# NanoPiAir_SDR_Shield_V1.net
KiCad netlist of a schematic drawn in Altium Designer
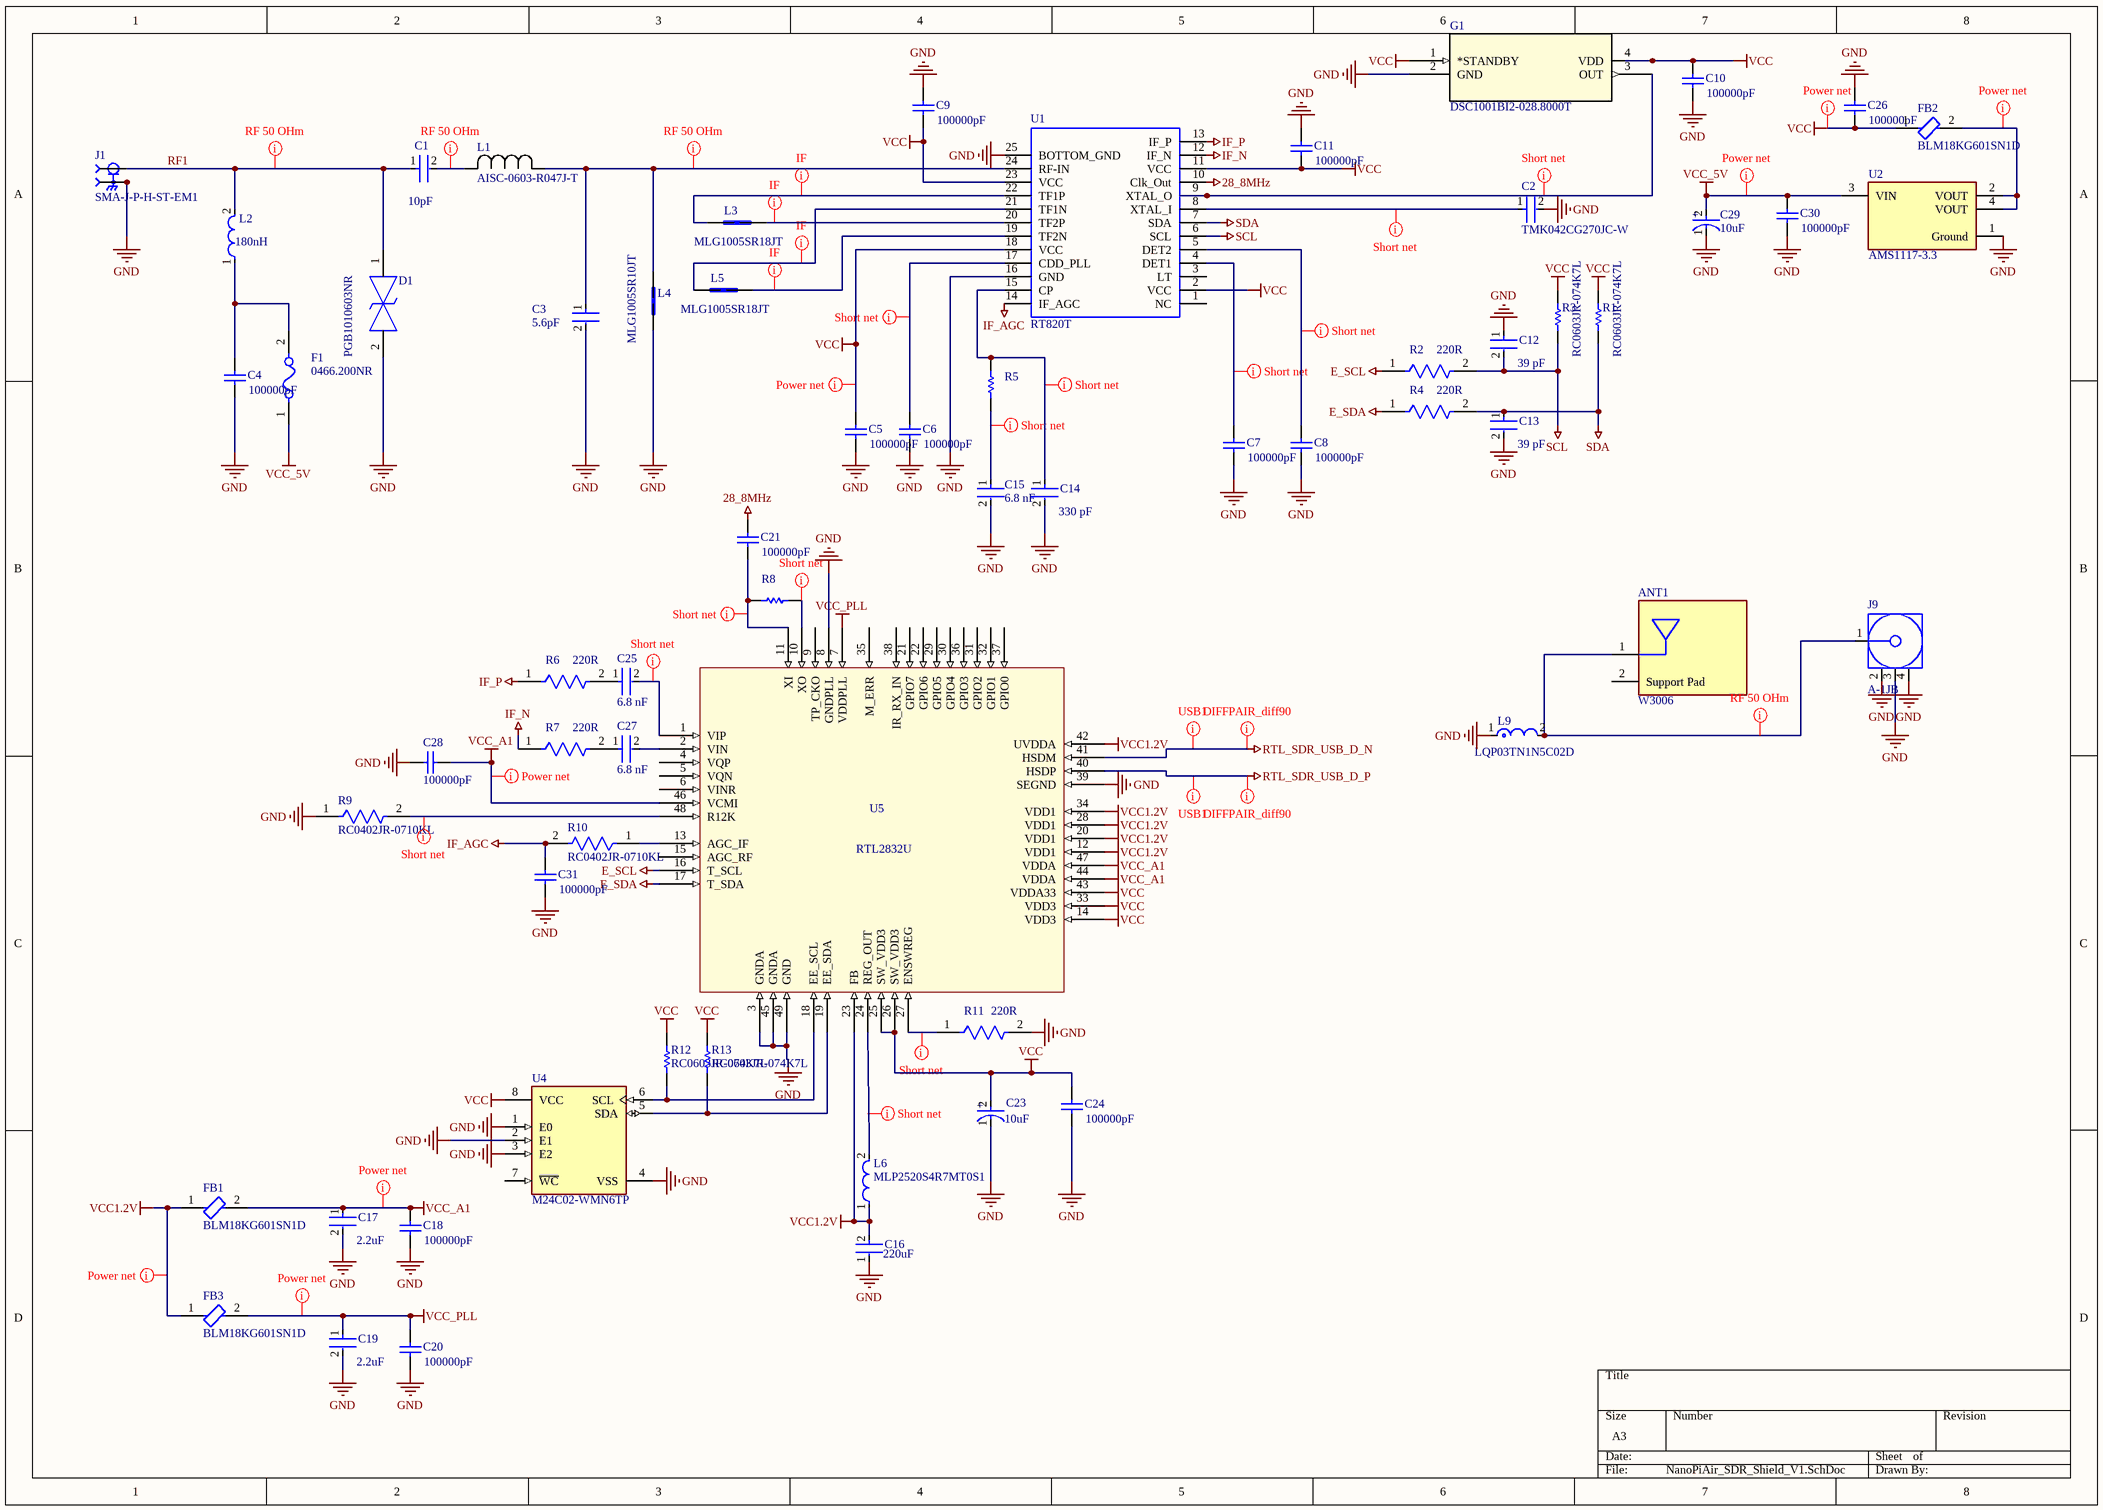
[diagram p0: NanoPiAir_SDR_Shield_V1.SchDoc]

(export (version "E")
  (design (tool "Eeschema 10.0.6"))
  (components
    (comp (ref "ANT1")
      (value "W3006")
      (footprint "FP-W3006-0")
      (description "RF ANT 2.4GHZ/5.5GHZ CHIP SLD")
      (libsource (lib "Altium Content Vault") (part "7e9f1c3ea5b015cef85830d8f377364"))
    )
    (comp (ref "C1")
      (value "GJM1555C1H100GB01D")
      (footprint "FP-GJM155-0_05-IPC_B")
      (description "Multi-Layer Ceramic Capacitor 10pF C0G  ±2% 0402 Paper T/R")
      (fields (field (name "CAPACITANCE") "10pF") (field (name "TOLERANCE") "2%"))
      (libsource (lib "Altium Content Vault") (part "02cd4be3c70576c341d710602a673aa"))
    )
    (comp (ref "C2")
      (value "TMK042CG270JC-W")
      (footprint "FP-01005-L_0_4_0_02-W_0_2-MFG")
      (description "None")
      (libsource (lib "Schlib1") (part "CMP-14477-000467-2"))
    )
    (comp (ref "C3")
      (value "GJM1555C1H5R6CB01D")
      (footprint "FP-GJM155-0_05-IPC_B")
      (description "Multi-Layer Ceramic Capacitor 5.6pF C0G  ±0.25pF 0402 Paper T/R")
      (fields (field (name "CAPACITANCE") "5.6pF") (field (name "VOLTAGE") "50V"))
      (libsource (lib "Altium Content Vault") (part "02cd4be3c70576c341d710602a673aa"))
    )
    (comp (ref "C4")
      (value "CL05B104KO5NNNC")
      (footprint "CAPC1050X55X23ML05T13")
      (description "Chip Capacitor, 100 nF, +/- 10%, 16 V, -55 to 125 degC, 0402 (1005 Metric), RoHS, Tape and Reel")
      (fields
        (field (name "MANUFACTURER") "Samsung Electro-Mechanics")
        (field (name "CAPACITANCE") "100000pF")
      )
      (libsource (lib "Altium Content Vault") (part "CAP-NP-2"))
    )
    (comp (ref "C5")
      (value "CL05B104KO5NNNC")
      (footprint "CAPC1050X55X23ML05T13")
      (description "Chip Capacitor, 100 nF, +/- 10%, 16 V, -55 to 125 degC, 0402 (1005 Metric), RoHS, Tape and Reel")
      (fields
        (field (name "MANUFACTURER") "Samsung Electro-Mechanics")
        (field (name "CAPACITANCE") "100000pF")
      )
      (libsource (lib "Altium Content Vault") (part "CAP-NP-2"))
    )
    (comp (ref "C6")
      (value "CL05B104KO5NNNC")
      (footprint "CAPC1050X55X23ML05T13")
      (description "Chip Capacitor, 100 nF, +/- 10%, 16 V, -55 to 125 degC, 0402 (1005 Metric), RoHS, Tape and Reel")
      (fields
        (field (name "MANUFACTURER") "Samsung Electro-Mechanics")
        (field (name "CAPACITANCE") "100000pF")
      )
      (libsource (lib "Altium Content Vault") (part "CAP-NP-2"))
    )
    (comp (ref "C7")
      (value "CL05B104KO5NNNC")
      (footprint "CAPC1050X55X23ML05T13")
      (description "Chip Capacitor, 100 nF, +/- 10%, 16 V, -55 to 125 degC, 0402 (1005 Metric), RoHS, Tape and Reel")
      (fields
        (field (name "MANUFACTURER") "Samsung Electro-Mechanics")
        (field (name "CAPACITANCE") "100000pF")
      )
      (libsource (lib "Altium Content Vault") (part "CAP-NP-2"))
    )
    (comp (ref "C8")
      (value "CL05B104KO5NNNC")
      (footprint "CAPC1050X55X23ML05T13")
      (description "Chip Capacitor, 100 nF, +/- 10%, 16 V, -55 to 125 degC, 0402 (1005 Metric), RoHS, Tape and Reel")
      (fields
        (field (name "MANUFACTURER") "Samsung Electro-Mechanics")
        (field (name "CAPACITANCE") "100000pF")
      )
      (libsource (lib "Altium Content Vault") (part "CAP-NP-2"))
    )
    (comp (ref "C9")
      (value "CL05B104KO5NNNC")
      (footprint "CAPC1050X55X23ML05T13")
      (description "Chip Capacitor, 100 nF, +/- 10%, 16 V, -55 to 125 degC, 0402 (1005 Metric), RoHS, Tape and Reel")
      (fields
        (field (name "MANUFACTURER") "Samsung Electro-Mechanics")
        (field (name "CAPACITANCE") "100000pF")
      )
      (libsource (lib "Altium Content Vault") (part "CAP-NP-2"))
    )
    (comp (ref "C10")
      (value "CL05B104KO5NNNC")
      (footprint "CAPC1050X55X23ML05T13")
      (description "Chip Capacitor, 100 nF, +/- 10%, 16 V, -55 to 125 degC, 0402 (1005 Metric), RoHS, Tape and Reel")
      (fields
        (field (name "MANUFACTURER") "Samsung Electro-Mechanics")
        (field (name "CAPACITANCE") "100000pF")
      )
      (libsource (lib "Altium Content Vault") (part "CAP-NP-2"))
    )
    (comp (ref "C11")
      (value "CL05B104KO5NNNC")
      (footprint "CAPC1050X55X23ML05T13")
      (description "Chip Capacitor, 100 nF, +/- 10%, 16 V, -55 to 125 degC, 0402 (1005 Metric), RoHS, Tape and Reel")
      (fields
        (field (name "MANUFACTURER") "Samsung Electro-Mechanics")
        (field (name "CAPACITANCE") "100000pF")
      )
      (libsource (lib "Altium Content Vault") (part "CAP-NP-2"))
    )
    (comp (ref "C12")
      (value "AC0402JRNPO9BN390")
      (footprint "FP-AC0402-0_5-MFG")
      (description "AC0402 39 pF NPO 5.00% 50 V")
      (fields
        (field (name "CAPACITANCE") "39 pF")
        (field (name "MANUFACTURER") "Yageo")
        (field (name "TOLERANCE") "0.05")
      )
      (libsource (lib "Altium Content Vault") (part "11868f565c42a9108669ba33697ecf6"))
    )
    (comp (ref "C13")
      (value "AC0402JRNPO9BN390")
      (footprint "FP-AC0402-0_5-MFG")
      (description "AC0402 39 pF NPO 5.00% 50 V")
      (fields
        (field (name "CAPACITANCE") "39 pF")
        (field (name "MANUFACTURER") "Yageo")
        (field (name "TOLERANCE") "0.05")
      )
      (libsource (lib "Altium Content Vault") (part "11868f565c42a9108669ba33697ecf6"))
    )
    (comp (ref "C14")
      (value "CC0402KRX7R7BB331")
      (footprint "FP-CC0402-MFG")
      (description "CC0402 330 pF X7R 10.00% 16 V")
      (fields
        (field (name "CAPACITANCE") "330 pF")
        (field (name "OCTOPART") "https://octopart.com/cc0402krx7r7bb331-yageo-87194285")
        (field (name "TOLERANCE") "0.1")
      )
      (libsource (lib "Altium Content Vault") (part "11868f565c42a9108669ba33697ecf6"))
    )
    (comp (ref "C15")
      (value "6.8 nF")
      (footprint "FP-CC0402-MFG")
      (description "CAP CER 6800PF 50V X7R 0402")
      (fields
        (field (name "MANUFACTURER") "YAGEO")
        (field (name "OCTOPART") "https://octopart.com/cc0402krx7r9bb682-yageo-9291871")
      )
      (libsource (lib "Altium Content Vault") (part "11868f565c42a9108669ba33697ecf6"))
    )
    (comp (ref "C16")
      (value "GRM31CR60J227ME11L")
      (footprint "FP-GRM31C-0_3-e0_3_0_9-IPC_C")
      (description "Chip Multilayer Ceramic Capacitors for General Purpose, 1206, 220uF, X5R, 15%, 20%, 6.3V")
      (fields (field (name "CAPACITANCE") "220uF") (field (name "TOLERANCE") "20%"))
      (libsource (lib "Altium Content Vault") (part "f23184f103b6ebe33a8c269c53dcba6"))
    )
    (comp (ref "C17")
      (value "GRM155R61A225KE95D")
      (footprint "FP-GRM155-0_05-MFG")
      (description "CAP CER 2.2UF 10V X5R 0402")
      (fields (field (name "CAPACITANCE") "2.2uF") (field (name "TOLERANCE") "10%"))
      (libsource (lib "Altium Content Vault") (part "b4654b650e69147ec39a6b967a45e02"))
    )
    (comp (ref "C18")
      (value "CL05B104KO5NNNC")
      (footprint "CAPC1050X55X23ML05T13")
      (description "Chip Capacitor, 100 nF, +/- 10%, 16 V, -55 to 125 degC, 0402 (1005 Metric), RoHS, Tape and Reel")
      (fields
        (field (name "MANUFACTURER") "Samsung Electro-Mechanics")
        (field (name "CAPACITANCE") "100000pF")
      )
      (libsource (lib "Altium Content Vault") (part "CAP-NP-2"))
    )
    (comp (ref "C19")
      (value "GRM155R61A225KE95D")
      (footprint "FP-GRM155-0_05-MFG")
      (description "CAP CER 2.2UF 10V X5R 0402")
      (fields (field (name "CAPACITANCE") "2.2uF") (field (name "TOLERANCE") "10%"))
      (libsource (lib "Altium Content Vault") (part "b4654b650e69147ec39a6b967a45e02"))
    )
    (comp (ref "C20")
      (value "CL05B104KO5NNNC")
      (footprint "CAPC1050X55X23ML05T13")
      (description "Chip Capacitor, 100 nF, +/- 10%, 16 V, -55 to 125 degC, 0402 (1005 Metric), RoHS, Tape and Reel")
      (fields
        (field (name "MANUFACTURER") "Samsung Electro-Mechanics")
        (field (name "CAPACITANCE") "100000pF")
      )
      (libsource (lib "Altium Content Vault") (part "CAP-NP-2"))
    )
    (comp (ref "C21")
      (value "CL05B104KO5NNNC")
      (footprint "CAPC1050X55X23ML05T13")
      (description "Chip Capacitor, 100 nF, +/- 10%, 16 V, -55 to 125 degC, 0402 (1005 Metric), RoHS, Tape and Reel")
      (fields
        (field (name "MANUFACTURER") "Samsung Electro-Mechanics")
        (field (name "CAPACITANCE") "100000pF")
      )
      (libsource (lib "Altium Content Vault") (part "CAP-NP-2"))
    )
    (comp (ref "C23")
      (value "TAJA106K010RNJ")
      (footprint "FP-TAJA-MFG")
      (description "10uF 10V  ±10% 3Ω 1206  SMD Tantalum Capacitor")
      (fields
        (field (name "TOLERANCE") "10%")
        (field (name "CAPACITANCE") "10uF")
        (field (name "VOLTAGE") "10V")
      )
      (libsource (lib "Altium Content Vault") (part "203bc49f2ac43e59fd269a8c329ed05"))
    )
    (comp (ref "C24")
      (value "CL05B104KO5NNNC")
      (footprint "CAPC1050X55X23ML05T13")
      (description "Chip Capacitor, 100 nF, +/- 10%, 16 V, -55 to 125 degC, 0402 (1005 Metric), RoHS, Tape and Reel")
      (fields
        (field (name "MANUFACTURER") "Samsung Electro-Mechanics")
        (field (name "CAPACITANCE") "100000pF")
      )
      (libsource (lib "Altium Content Vault") (part "CAP-NP-2"))
    )
    (comp (ref "C25")
      (value "6.8 nF")
      (footprint "FP-CC0402-MFG")
      (description "CAP CER 6800PF 50V X7R 0402")
      (fields
        (field (name "MANUFACTURER") "YAGEO")
        (field (name "OCTOPART") "https://octopart.com/cc0402krx7r9bb682-yageo-9291871")
      )
      (libsource (lib "Altium Content Vault") (part "11868f565c42a9108669ba33697ecf6"))
    )
    (comp (ref "C26")
      (value "CL05B104KO5NNNC")
      (footprint "CAPC1050X55X23ML05T13")
      (description "Chip Capacitor, 100 nF, +/- 10%, 16 V, -55 to 125 degC, 0402 (1005 Metric), RoHS, Tape and Reel")
      (fields
        (field (name "MANUFACTURER") "Samsung Electro-Mechanics")
        (field (name "CAPACITANCE") "100000pF")
      )
      (libsource (lib "Altium Content Vault") (part "CAP-NP-2"))
    )
    (comp (ref "C27")
      (value "6.8 nF")
      (footprint "FP-CC0402-MFG")
      (description "CAP CER 6800PF 50V X7R 0402")
      (fields
        (field (name "MANUFACTURER") "YAGEO")
        (field (name "OCTOPART") "https://octopart.com/cc0402krx7r9bb682-yageo-9291871")
      )
      (libsource (lib "Altium Content Vault") (part "11868f565c42a9108669ba33697ecf6"))
    )
    (comp (ref "C28")
      (value "CL05B104KO5NNNC")
      (footprint "CAPC1050X55X23ML05T13")
      (description "Chip Capacitor, 100 nF, +/- 10%, 16 V, -55 to 125 degC, 0402 (1005 Metric), RoHS, Tape and Reel")
      (fields
        (field (name "MANUFACTURER") "Samsung Electro-Mechanics")
        (field (name "CAPACITANCE") "100000pF")
      )
      (libsource (lib "Altium Content Vault") (part "CAP-NP-2"))
    )
    (comp (ref "C29")
      (value "TAJA106K010RNJ")
      (footprint "FP-TAJA-MFG")
      (description "10uF 10V  ±10% 3Ω 1206  SMD Tantalum Capacitor")
      (fields
        (field (name "TOLERANCE") "10%")
        (field (name "CAPACITANCE") "10uF")
        (field (name "VOLTAGE") "10V")
      )
      (libsource (lib "Altium Content Vault") (part "203bc49f2ac43e59fd269a8c329ed05"))
    )
    (comp (ref "C30")
      (value "CL05B104KO5NNNC")
      (footprint "CAPC1050X55X23ML05T13")
      (description "Chip Capacitor, 100 nF, +/- 10%, 16 V, -55 to 125 degC, 0402 (1005 Metric), RoHS, Tape and Reel")
      (fields
        (field (name "MANUFACTURER") "Samsung Electro-Mechanics")
        (field (name "CAPACITANCE") "100000pF")
      )
      (libsource (lib "Altium Content Vault") (part "CAP-NP-2"))
    )
    (comp (ref "C31")
      (value "CL05B104KO5NNNC")
      (footprint "CAPC1050X55X23ML05T13")
      (description "Chip Capacitor, 100 nF, +/- 10%, 16 V, -55 to 125 degC, 0402 (1005 Metric), RoHS, Tape and Reel")
      (fields
        (field (name "MANUFACTURER") "Samsung Electro-Mechanics")
        (field (name "CAPACITANCE") "100000pF")
      )
      (libsource (lib "Altium Content Vault") (part "CAP-NP-2"))
    )
    (comp (ref "D1")
      (value "PGB1010603NR")
      (footprint "PGB1010603MR")
      (description "ESD Suppressors / TVS Diodes 0603 24VDC .06pF")
      (fields (field (name "MOUSER PART NUMBER") "576-PGB1010603NR"))
      (libsource (lib "Schlib1") (part "PGB1010603NR"))
    )
    (comp (ref "F1")
      (value "0466.200NR")
      (footprint "FP-0466-MFG")
      (description "FUSE BOARD MNT 200MA 125VAC/VDC")
      (libsource (lib "Altium Content Vault") (part "5bcf9b9f640e542cf0359d10258e979"))
    )
    (comp (ref "FB1")
      (value "BLM18KG601SN1D")
      (footprint "FP-BLM18-0_15-t0_8-IPC_A")
      (description "Chip Ferrite Bead, 0603, 600Ω @ 100MHz, 0.15Ω, 25%, 1.3A")
      (fields (field (name "TOLERANCE") "25%"))
      (libsource (lib "Altium Content Vault") (part "5f30dd21d616792df468990f7003faa"))
    )
    (comp (ref "FB2")
      (value "BLM18KG601SN1D")
      (footprint "FP-BLM18-0_15-t0_8-IPC_A")
      (description "Chip Ferrite Bead, 0603, 600Ω @ 100MHz, 0.15Ω, 25%, 1.3A")
      (fields (field (name "TOLERANCE") "25%"))
      (libsource (lib "Altium Content Vault") (part "5f30dd21d616792df468990f7003faa"))
    )
    (comp (ref "FB3")
      (value "BLM18KG601SN1D")
      (footprint "FP-BLM18-0_15-t0_8-IPC_A")
      (description "Chip Ferrite Bead, 0603, 600Ω @ 100MHz, 0.15Ω, 25%, 1.3A")
      (fields (field (name "TOLERANCE") "25%"))
      (libsource (lib "Altium Content Vault") (part "5f30dd21d616792df468990f7003faa"))
    )
    (comp (ref "G1")
      (value "DSC1001BI2-028.8000T")
      (footprint "CDFN4_5X3P2_MCH")
      (description "No Description Available")
      (fields (field (name "COPYRIGHT") "Copyright (C) 2023 Ultra Librarian. All rights reserved."))
      (libsource (lib "Schlib1") (part "DSC1001BI2-028.8000T"))
    )
    (comp (ref "J1")
      (value "SMA-J-P-H-ST-EM1")
      (footprint "SAMTEC_SMA-J-P-H-ST-EM1")
      (description "SMA Connector Jack, Female Socket 50Ohm Board Edge, End Launch Solder")
      (libsource (lib "Schlib1") (part "SMA-J-P-H-ST-EM1"))
    )
    (comp (ref "J9")
      (value "A-1JB")
      (footprint "AMPH-A-1JB_V")
      (description "AMC PCB Jack, 0 to 60 GHz, 60 V, -40 to 90 degC, 4-Pin SMD, RoHS, Tape and Reel")
      (fields (field (name "TOLERANCE") "10%"))
      (libsource (lib "Altium Content Vault") (part "CN-S-3F-RF4"))
    )
    (comp (ref "L1")
      (value "AISC-0603-R047J-T")
      (footprint "AISC-0603_ABR")
      (description "No Description Available")
      (fields (field (name "COPYRIGHT") "Copyright (C) 2023 Ultra Librarian. All rights reserved."))
      (libsource (lib "Schlib1") (part "AISC-0603-R047J-T"))
    )
    (comp (ref "L2")
      (value "LQM18NNR18K00D")
      (footprint "FP-LQM18NN_00-IPC_C")
      (description "Multilayer Type Inductor for General Circuits, 0603 (1608), 180nH, 10%, 0.6Ω, 50mA")
      (fields (field (name "INDUCTANCE") "180nH") (field (name "TOLERANCE") "10%"))
      (libsource (lib "Altium Content Vault") (part "725321dda6339637d4d059423bc1c3c"))
    )
    (comp (ref "L3")
      (value "MLG1005SR18JT")
      (footprint "CAPC1005X55N")
      (description "Ind High Frequency Chip Unshielded Multi-Layer 180nH 5% 100MHz 8Q-Factor Ceramic 150mA 0402 T/R")
      (libsource (lib "Schlib1") (part "MLG1005SR18JT"))
    )
    (comp (ref "L4")
      (value "MLG1005SR10JT")
      (footprint "CAPC1005X55N")
      (description "Ind High Frequency Chip Unshielded Multi-Layer 180nH 5% 100MHz 8Q-Factor Ceramic 150mA 0402 T/R")
      (fields (field (name "MP") "MLG1005SR18JT"))
      (libsource (lib "") (part "MLG1005SR18JT_1"))
    )
    (comp (ref "L5")
      (value "MLG1005SR18JT")
      (footprint "CAPC1005X55N")
      (description "Ind High Frequency Chip Unshielded Multi-Layer 180nH 5% 100MHz 8Q-Factor Ceramic 150mA 0402 T/R")
      (libsource (lib "Schlib1") (part "MLG1005SR18JT"))
    )
    (comp (ref "L6")
      (value "MLP2520S4R7MT0S1")
      (footprint "FP-MLP2520M-IPC_C")
      (description "Shielded Multilayer Inductor 4.7uH ±20% 1000mA 169mΩ SMD 1008")
      (fields (field (name "TOLERANCE") "20%"))
      (libsource (lib "Altium Content Vault") (part "725321dda6339637d4d059423bc1c3c"))
    )
    (comp (ref "L9")
      (value "LQP03TN1N5C02D")
      (footprint "FP-LQP03TG_02-IPC_A")
      (description "Film type RF Inductor 1.5nH ±0.2nH 600mA 0.15Ω 0201 (0603)")
      (libsource (lib "Altium Content Vault") (part "4cc4b267dca4c8e51f7102f422741d8"))
    )
    (comp (ref "R1")
      (value "RC0603JR-074K7L")
      (footprint "RESC1608X55X25ML10T15")
      (description "Chip Resistor, 4.7 KOhm, +/- 5%, 100 mW, -55 to 155 degC, 0603 (1608 Metric), RoHS, Tape and Reel")
      (fields (field (name "TOLERANCE") "5%") (field (name "MANUFACTURER") "Yageo"))
      (libsource (lib "Altium Content Vault") (part "RES-2"))
    )
    (comp (ref "R2")
      (value "AC0402FR-07220RL")
      (footprint "FP-AC0402-IPC_C")
      (description "RES 220Ω ±1% 0.063W 0402")
      (fields (field (name "RESISTANCE") "220R") (field (name "TOLERANCE") "1%"))
      (libsource (lib "Altium Content Vault") (part "1029c3af85768c4190bb7ad29bc67b5"))
    )
    (comp (ref "R3")
      (value "RC0603JR-074K7L")
      (footprint "RESC1608X55X25ML10T15")
      (description "Chip Resistor, 4.7 KOhm, +/- 5%, 100 mW, -55 to 155 degC, 0603 (1608 Metric), RoHS, Tape and Reel")
      (fields (field (name "TOLERANCE") "5%") (field (name "MANUFACTURER") "Yageo"))
      (libsource (lib "Altium Content Vault") (part "RES-2"))
    )
    (comp (ref "R4")
      (value "AC0402FR-07220RL")
      (footprint "FP-AC0402-IPC_C")
      (description "RES 220Ω ±1% 0.063W 0402")
      (fields (field (name "RESISTANCE") "220R") (field (name "TOLERANCE") "1%"))
      (libsource (lib "Altium Content Vault") (part "1029c3af85768c4190bb7ad29bc67b5"))
    )
    (comp (ref "R5")
      (value "RK73H1ETTP1801F")
      (footprint "RESC1005X40X25ML10T10")
      (fields (field (name "MANUFACTURER") "KOA Speer"))
      (libsource (lib "Altium Content Vault") (part "RES"))
    )
    (comp (ref "R6")
      (value "AC0402FR-07220RL")
      (footprint "FP-AC0402-IPC_C")
      (description "RES 220Ω ±1% 0.063W 0402")
      (fields (field (name "RESISTANCE") "220R") (field (name "TOLERANCE") "1%"))
      (libsource (lib "Altium Content Vault") (part "1029c3af85768c4190bb7ad29bc67b5"))
    )
    (comp (ref "R7")
      (value "AC0402FR-07220RL")
      (footprint "FP-AC0402-IPC_C")
      (description "RES 220Ω ±1% 0.063W 0402")
      (fields (field (name "RESISTANCE") "220R") (field (name "TOLERANCE") "1%"))
      (libsource (lib "Altium Content Vault") (part "1029c3af85768c4190bb7ad29bc67b5"))
    )
    (comp (ref "R8")
      (value "RC0402JR-07150KL")
      (footprint "RESC1005X40X25ML05T10")
      (fields (field (name "MANUFACTURER") "Yageo / Phycomp"))
      (libsource (lib "Altium Content Vault") (part "RES"))
    )
    (comp (ref "R9")
      (value "RC0402JR-0710KL")
      (footprint "FP-RC0402-0_4-IPC_C")
      (description "RES 10K OHM 5% 1/16W 0402")
      (fields (field (name "TOLERANCE") "5%"))
      (libsource (lib "Altium Content Vault") (part "1029c3af85768c4190bb7ad29bc67b5"))
    )
    (comp (ref "R10")
      (value "RC0402JR-0710KL")
      (footprint "FP-RC0402-0_4-IPC_C")
      (description "RES 10K OHM 5% 1/16W 0402")
      (fields (field (name "TOLERANCE") "5%"))
      (libsource (lib "Altium Content Vault") (part "1029c3af85768c4190bb7ad29bc67b5"))
    )
    (comp (ref "R11")
      (value "AC0402FR-07220RL")
      (footprint "FP-AC0402-IPC_C")
      (description "RES 220Ω ±1% 0.063W 0402")
      (fields (field (name "RESISTANCE") "220R") (field (name "TOLERANCE") "1%"))
      (libsource (lib "Altium Content Vault") (part "1029c3af85768c4190bb7ad29bc67b5"))
    )
    (comp (ref "R12")
      (value "RC0603JR-074K7L")
      (footprint "RESC1608X55X25ML10T15")
      (description "Chip Resistor, 4.7 KOhm, +/- 5%, 100 mW, -55 to 155 degC, 0603 (1608 Metric), RoHS, Tape and Reel")
      (fields (field (name "TOLERANCE") "5%") (field (name "MANUFACTURER") "Yageo"))
      (libsource (lib "Altium Content Vault") (part "RES-2"))
    )
    (comp (ref "R13")
      (value "RC0603JR-074K7L")
      (footprint "RESC1608X55X25ML10T15")
      (description "Chip Resistor, 4.7 KOhm, +/- 5%, 100 mW, -55 to 155 degC, 0603 (1608 Metric), RoHS, Tape and Reel")
      (fields (field (name "TOLERANCE") "5%") (field (name "MANUFACTURER") "Yageo"))
      (libsource (lib "Altium Content Vault") (part "RES-2"))
    )
    (comp (ref "U1")
      (value "RT820T")
      (footprint "QFN24_4X4_SIL-L")
      (description "High Performance Low Power\r\nAdvanced Digital TV Silicon Tuner")
      (libsource (lib "Schlib1") (part "RT820T-QFN24"))
    )
    (comp (ref "U2")
      (value "AMS1117-3.3")
      (footprint "FP-AMS1117-IPC_C")
      (description "LDO Voltage Regulators 1A, 3.3V")
      (fields
        (field (name "OCTOPART") "https://octopart.com/ams1117-3.3-advanced+monolithic+systems-25899300")
        (field (name "MANUFACTURER") "Advanced Monolithic Systems")
      )
      (libsource (lib "Altium Content Vault") (part "8bdbb5f8e77002000e30dd2845d0354"))
    )
    (comp (ref "U4")
      (value "M24C02-WMN6TP")
      (footprint "FP-SO8N-SO-A-MFG")
      (description "IC EEPROM 2K I2C 400KHZ 8SO")
      (fields
        (field (name "MANUFACTURER") "STMicroelectronics")
        (field (name "OCTOPART") "https://octopart.com/m24c02-wmn6tp-stmicroelectronics-55404516")
      )
      (libsource (lib "Altium Content Vault") (part "6c91e1c1613830ec3abd94c18390ae3"))
    )
    (comp (ref "U5")
      (value "RTL2832U")
      (footprint "QFN40P600X600X84_HS-49N")
      (description "RTL2832U DVB-T COFDM Demodulator + USB 2.0")
      (fields (field (name "MANUFACTURER") "Realtek") (field (name "PUBLISHER") "ftg"))
      (libsource (lib "Schlib1") (part "RTL2832U"))
    )
  )
  (nets
    (net (code "1") (name "/RF1") (class "Default")
      (node (ref "C1") (pin "1") (pinfunction "1_1") (pintype "passive"))
      (node (ref "D1") (pin "1") (pinfunction "1_1") (pintype "passive"))
      (node (ref "J1") (pin "1") (pinfunction "1_1") (pintype "passive"))
      (node (ref "L2") (pin "2") (pinfunction "2_2") (pintype "passive"))
    )
    (net (code "2") (name "28_8MHz") (class "Default")
      (node (ref "C21") (pin "2") (pinfunction "2_2") (pintype "passive"))
      (node (ref "U1") (pin "10") (pinfunction "Clk_Out_10") (pintype "passive"))
    )
    (net (code "3") (name "E_SCL") (class "Default")
      (node (ref "R2") (pin "1") (pinfunction "1_1") (pintype "passive"))
      (node (ref "U5") (pin "16") (pinfunction "T_SCL_16") (pintype "input"))
    )
    (net (code "4") (name "E_SDA") (class "Default")
      (node (ref "R4") (pin "1") (pinfunction "1_1") (pintype "passive"))
      (node (ref "U5") (pin "17") (pinfunction "T_SDA_17") (pintype "input"))
    )
    (net (code "5") (name "GND") (class "Default")
      (node (ref "C10") (pin "1") (pinfunction "1_1") (pintype "passive"))
      (node (ref "C11") (pin "2") (pinfunction "2_2") (pintype "passive"))
      (node (ref "C12") (pin "1") (pinfunction "1_1") (pintype "passive"))
      (node (ref "C13") (pin "2") (pinfunction "2_2") (pintype "passive"))
      (node (ref "C14") (pin "2") (pinfunction "2_2") (pintype "passive"))
      (node (ref "C15") (pin "2") (pinfunction "2_2") (pintype "passive"))
      (node (ref "C16") (pin "1") (pinfunction "1_1") (pintype "passive"))
      (node (ref "C17") (pin "2") (pinfunction "2_2") (pintype "passive"))
      (node (ref "C18") (pin "1") (pinfunction "1_1") (pintype "passive"))
      (node (ref "C19") (pin "2") (pinfunction "2_2") (pintype "passive"))
      (node (ref "C2") (pin "2") (pinfunction "2_2") (pintype "passive"))
      (node (ref "C20") (pin "1") (pinfunction "1_1") (pintype "passive"))
      (node (ref "C23") (pin "1") (pinfunction "C_1") (pintype "passive"))
      (node (ref "C24") (pin "1") (pinfunction "1_1") (pintype "passive"))
      (node (ref "C26") (pin "2") (pinfunction "2_2") (pintype "passive"))
      (node (ref "C28") (pin "2") (pinfunction "2_2") (pintype "passive"))
      (node (ref "C29") (pin "1") (pinfunction "C_1") (pintype "passive"))
      (node (ref "C3") (pin "2") (pinfunction "2_2") (pintype "passive"))
      (node (ref "C30") (pin "1") (pinfunction "1_1") (pintype "passive"))
      (node (ref "C31") (pin "1") (pinfunction "1_1") (pintype "passive"))
      (node (ref "C4") (pin "1") (pinfunction "1_1") (pintype "passive"))
      (node (ref "C5") (pin "1") (pinfunction "1_1") (pintype "passive"))
      (node (ref "C6") (pin "1") (pinfunction "1_1") (pintype "passive"))
      (node (ref "C7") (pin "1") (pinfunction "1_1") (pintype "passive"))
      (node (ref "C8") (pin "1") (pinfunction "1_1") (pintype "passive"))
      (node (ref "C9") (pin "2") (pinfunction "2_2") (pintype "passive"))
      (node (ref "D1") (pin "2") (pinfunction "2_2") (pintype "passive"))
      (node (ref "G1") (pin "2") (pinfunction "GND_2") (pintype "passive"))
      (node (ref "J1") (pin "2_1") (pinfunction "2_2_1") (pintype "passive"))
      (node (ref "J1") (pin "2_2") (pinfunction "2_2_2") (pintype "passive"))
      (node (ref "J1") (pin "3_1") (pinfunction "2_3_1") (pintype "passive"))
      (node (ref "J1") (pin "3_2") (pinfunction "2_3_2") (pintype "passive"))
      (node (ref "J9") (pin "2") (pinfunction "2_2") (pintype "passive"))
      (node (ref "J9") (pin "3") (pinfunction "3_3") (pintype "passive"))
      (node (ref "J9") (pin "4") (pinfunction "4_4") (pintype "passive"))
      (node (ref "L4") (pin "1") (pinfunction "1_1") (pintype "passive"))
      (node (ref "L9") (pin "1") (pinfunction "1_1") (pintype "passive"))
      (node (ref "R11") (pin "2") (pinfunction "2_2") (pintype "passive"))
      (node (ref "R9") (pin "1") (pinfunction "1_1") (pintype "passive"))
      (node (ref "U1") (pin "16") (pinfunction "GND_16") (pintype "passive"))
      (node (ref "U1") (pin "25") (pinfunction "BOTTOM_GND_25") (pintype "passive"))
      (node (ref "U2") (pin "1") (pinfunction "Ground_1") (pintype "power_in"))
      (node (ref "U4") (pin "1") (pinfunction "E0_1") (pintype "input"))
      (node (ref "U4") (pin "2") (pinfunction "E1_2") (pintype "input"))
      (node (ref "U4") (pin "3") (pinfunction "E2_3") (pintype "input"))
      (node (ref "U4") (pin "4") (pinfunction "VSS_4") (pintype "power_in"))
      (node (ref "U5") (pin "3") (pinfunction "GNDA_3") (pintype "input"))
      (node (ref "U5") (pin "39") (pinfunction "SEGND_39") (pintype "input"))
      (node (ref "U5") (pin "45") (pinfunction "GNDA_45") (pintype "input"))
      (node (ref "U5") (pin "49") (pinfunction "GND_49") (pintype "input"))
      (node (ref "U5") (pin "8") (pinfunction "GNDPLL_8") (pintype "input"))
    )
    (net (code "6") (name "IF_AGC") (class "Default")
      (node (ref "C31") (pin "2") (pinfunction "2_2") (pintype "passive"))
      (node (ref "R10") (pin "2") (pinfunction "2_2") (pintype "passive"))
      (node (ref "U1") (pin "14") (pinfunction "IF_AGC_14") (pintype "passive"))
    )
    (net (code "7") (name "IF_N") (class "Default")
      (node (ref "R7") (pin "1") (pinfunction "1_1") (pintype "passive"))
      (node (ref "U1") (pin "12") (pinfunction "IF_N_12") (pintype "passive"))
    )
    (net (code "8") (name "IF_P") (class "Default")
      (node (ref "R6") (pin "1") (pinfunction "1_1") (pintype "passive"))
      (node (ref "U1") (pin "13") (pinfunction "IF_P_13") (pintype "passive"))
    )
    (net (code "9") (name "Net-(ANT1-Feed)") (class "Default")
      (node (ref "ANT1") (pin "1") (pinfunction "Feed_1") (pintype "passive"))
      (node (ref "J9") (pin "1") (pinfunction "1_1") (pintype "passive"))
      (node (ref "L9") (pin "2") (pinfunction "2_2") (pintype "passive"))
    )
    (net (code "10") (name "Net-(C1-Pad2)") (class "Default")
      (node (ref "C1") (pin "2") (pinfunction "2_2") (pintype "passive"))
      (node (ref "L1") (pin "2") (pinfunction "2_2") (pintype "passive"))
    )
    (net (code "11") (name "Net-(C4-Pad2)") (class "Default")
      (node (ref "C4") (pin "2") (pinfunction "2_2") (pintype "passive"))
      (node (ref "F1") (pin "2") (pinfunction "2_2") (pintype "passive"))
      (node (ref "L2") (pin "1") (pinfunction "1_1") (pintype "passive"))
    )
    (net (code "12") (name "Net-(C15-Pad1)") (class "Default")
      (node (ref "C15") (pin "1") (pinfunction "1_1") (pintype "passive"))
      (node (ref "R5") (pin "1") (pinfunction "1_1") (pintype "passive"))
    )
    (net (code "13") (name "Net-(C25-Pad1)") (class "Default")
      (node (ref "C25") (pin "1") (pinfunction "1_1") (pintype "passive"))
      (node (ref "R6") (pin "2") (pinfunction "2_2") (pintype "passive"))
    )
    (net (code "14") (name "Net-(C27-Pad1)") (class "Default")
      (node (ref "C27") (pin "1") (pinfunction "1_1") (pintype "passive"))
      (node (ref "R7") (pin "2") (pinfunction "2_2") (pintype "passive"))
    )
    (net (code "15") (name "Net-(FB2-Pad2)") (class "Default")
      (node (ref "FB2") (pin "2") (pinfunction "2_2") (pintype "passive"))
      (node (ref "U2") (pin "2") (pinfunction "VOUT_2") (pintype "passive"))
      (node (ref "U2") (pin "4") (pinfunction "VOUT_4") (pintype "passive"))
    )
    (net (code "16") (name "Net-(G1-OUT)") (class "Default")
      (node (ref "G1") (pin "3") (pinfunction "OUT_3") (pintype "output"))
      (node (ref "U1") (pin "9") (pinfunction "XTAL_O_9") (pintype "passive"))
    )
    (net (code "17") (name "Net-(U1-CDD_PLL)") (class "Default")
      (node (ref "C6") (pin "2") (pinfunction "2_2") (pintype "passive"))
      (node (ref "U1") (pin "17") (pinfunction "CDD_PLL_17") (pintype "passive"))
    )
    (net (code "18") (name "Net-(U1-CP)") (class "Default")
      (node (ref "C14") (pin "1") (pinfunction "1_1") (pintype "passive"))
      (node (ref "R5") (pin "2") (pinfunction "2_2") (pintype "passive"))
      (node (ref "U1") (pin "15") (pinfunction "CP_15") (pintype "passive"))
    )
    (net (code "19") (name "Net-(U1-DET1)") (class "Default")
      (node (ref "C7") (pin "2") (pinfunction "2_2") (pintype "passive"))
      (node (ref "U1") (pin "4") (pinfunction "DET1_4") (pintype "passive"))
    )
    (net (code "20") (name "Net-(U1-DET2)") (class "Default")
      (node (ref "C8") (pin "2") (pinfunction "2_2") (pintype "passive"))
      (node (ref "U1") (pin "5") (pinfunction "DET2_5") (pintype "passive"))
    )
    (net (code "21") (name "Net-(U1-RF-IN)") (class "Default")
      (node (ref "C3") (pin "1") (pinfunction "1_1") (pintype "passive"))
      (node (ref "L1") (pin "1") (pinfunction "1_1") (pintype "passive"))
      (node (ref "L4") (pin "2") (pinfunction "2_2") (pintype "passive"))
      (node (ref "U1") (pin "24") (pinfunction "RF-IN_24") (pintype "passive"))
    )
    (net (code "22") (name "Net-(U1-TF1N)") (class "Default")
      (node (ref "L5") (pin "1") (pinfunction "1_1") (pintype "passive"))
      (node (ref "U1") (pin "21") (pinfunction "TF1N_21") (pintype "passive"))
    )
    (net (code "23") (name "Net-(U1-TF1P)") (class "Default")
      (node (ref "L3") (pin "1") (pinfunction "1_1") (pintype "passive"))
      (node (ref "U1") (pin "22") (pinfunction "TF1P_22") (pintype "passive"))
    )
    (net (code "24") (name "Net-(U1-TF2N)") (class "Default")
      (node (ref "L5") (pin "2") (pinfunction "2_2") (pintype "passive"))
      (node (ref "U1") (pin "19") (pinfunction "TF2N_19") (pintype "passive"))
    )
    (net (code "25") (name "Net-(U1-TF2P)") (class "Default")
      (node (ref "L3") (pin "2") (pinfunction "2_2") (pintype "passive"))
      (node (ref "U1") (pin "20") (pinfunction "TF2P_20") (pintype "passive"))
    )
    (net (code "26") (name "Net-(U1-XTAL_I)") (class "Default")
      (node (ref "C2") (pin "1") (pinfunction "1_1") (pintype "passive"))
      (node (ref "U1") (pin "8") (pinfunction "XTAL_I_8") (pintype "passive"))
    )
    (net (code "27") (name "Net-(U4-SCL)") (class "Default")
      (node (ref "R12") (pin "2") (pinfunction "2_2") (pintype "passive"))
      (node (ref "U4") (pin "6") (pinfunction "SCL_6") (pintype "input"))
      (node (ref "U5") (pin "18") (pinfunction "EE_SCL_18") (pintype "input"))
    )
    (net (code "28") (name "Net-(U4-SDA)") (class "Default")
      (node (ref "R13") (pin "2") (pinfunction "2_2") (pintype "passive"))
      (node (ref "U4") (pin "5") (pinfunction "SDA_5") (pintype "bidirectional"))
      (node (ref "U5") (pin "19") (pinfunction "EE_SDA_19") (pintype "input"))
    )
    (net (code "29") (name "Net-(U5-AGC_IF)") (class "Default")
      (node (ref "R10") (pin "1") (pinfunction "1_1") (pintype "passive"))
      (node (ref "U5") (pin "13") (pinfunction "AGC_IF_13") (pintype "input"))
    )
    (net (code "30") (name "Net-(U5-ENSWREG)") (class "Default")
      (node (ref "R11") (pin "1") (pinfunction "1_1") (pintype "passive"))
      (node (ref "U5") (pin "27") (pinfunction "ENSWREG_27") (pintype "input"))
    )
    (net (code "31") (name "Net-(U5-R12K)") (class "Default")
      (node (ref "R9") (pin "2") (pinfunction "2_2") (pintype "passive"))
      (node (ref "U5") (pin "48") (pinfunction "R12K_48") (pintype "input"))
    )
    (net (code "32") (name "Net-(U5-REG_OUT)") (class "Default")
      (node (ref "L6") (pin "2") (pinfunction "2_2") (pintype "passive"))
      (node (ref "U5") (pin "24") (pinfunction "REG_OUT_24") (pintype "input"))
    )
    (net (code "33") (name "Net-(U5-VIN)") (class "Default")
      (node (ref "C27") (pin "2") (pinfunction "2_2") (pintype "passive"))
      (node (ref "U5") (pin "2") (pinfunction "VIN_2") (pintype "input"))
    )
    (net (code "34") (name "Net-(U5-VIP)") (class "Default")
      (node (ref "C25") (pin "2") (pinfunction "2_2") (pintype "passive"))
      (node (ref "U5") (pin "1") (pinfunction "VIP_1") (pintype "input"))
    )
    (net (code "35") (name "Net-(U5-XI)") (class "Default")
      (node (ref "C21") (pin "1") (pinfunction "1_1") (pintype "passive"))
      (node (ref "R8") (pin "2") (pinfunction "2_2") (pintype "passive"))
      (node (ref "U5") (pin "11") (pinfunction "XI_11") (pintype "input"))
    )
    (net (code "36") (name "Net-(U5-XO)") (class "Default")
      (node (ref "R8") (pin "1") (pinfunction "1_1") (pintype "passive"))
      (node (ref "U5") (pin "10") (pinfunction "XO_10") (pintype "input"))
    )
    (net (code "37") (name "RTL_SDR_USB_D_N") (class "Default")
      (node (ref "U5") (pin "41") (pinfunction "HSDM_41") (pintype "input"))
    )
    (net (code "38") (name "RTL_SDR_USB_D_P") (class "Default")
      (node (ref "U5") (pin "40") (pinfunction "HSDP_40") (pintype "input"))
    )
    (net (code "39") (name "SCL") (class "Default")
      (node (ref "C12") (pin "2") (pinfunction "2_2") (pintype "passive"))
      (node (ref "R2") (pin "2") (pinfunction "2_2") (pintype "passive"))
      (node (ref "R3") (pin "2") (pinfunction "2_2") (pintype "passive"))
      (node (ref "U1") (pin "6") (pinfunction "SCL_6") (pintype "passive"))
    )
    (net (code "40") (name "SDA") (class "Default")
      (node (ref "C13") (pin "1") (pinfunction "1_1") (pintype "passive"))
      (node (ref "R1") (pin "2") (pinfunction "2_2") (pintype "passive"))
      (node (ref "R4") (pin "2") (pinfunction "2_2") (pintype "passive"))
      (node (ref "U1") (pin "7") (pinfunction "SDA_7") (pintype "passive"))
    )
    (net (code "41") (name "VCC") (class "Default")
      (node (ref "C10") (pin "2") (pinfunction "2_2") (pintype "passive"))
      (node (ref "C11") (pin "1") (pinfunction "1_1") (pintype "passive"))
      (node (ref "C23") (pin "2") (pinfunction "A_2") (pintype "passive"))
      (node (ref "C24") (pin "2") (pinfunction "2_2") (pintype "passive"))
      (node (ref "C26") (pin "1") (pinfunction "1_1") (pintype "passive"))
      (node (ref "C5") (pin "2") (pinfunction "2_2") (pintype "passive"))
      (node (ref "C9") (pin "1") (pinfunction "1_1") (pintype "passive"))
      (node (ref "FB2") (pin "1") (pinfunction "1_1") (pintype "passive"))
      (node (ref "G1") (pin "1") (pinfunction "*STANDBY_1") (pintype "input"))
      (node (ref "G1") (pin "4") (pinfunction "VDD_4") (pintype "power_in"))
      (node (ref "R1") (pin "1") (pinfunction "1_1") (pintype "passive"))
      (node (ref "R12") (pin "1") (pinfunction "1_1") (pintype "passive"))
      (node (ref "R13") (pin "1") (pinfunction "1_1") (pintype "passive"))
      (node (ref "R3") (pin "1") (pinfunction "1_1") (pintype "passive"))
      (node (ref "U1") (pin "11") (pinfunction "VCC_11") (pintype "passive"))
      (node (ref "U1") (pin "18") (pinfunction "VCC_18") (pintype "passive"))
      (node (ref "U1") (pin "2") (pinfunction "VCC_2") (pintype "passive"))
      (node (ref "U1") (pin "23") (pinfunction "VCC_23") (pintype "passive"))
      (node (ref "U4") (pin "8") (pinfunction "VCC_8") (pintype "power_in"))
      (node (ref "U5") (pin "14") (pinfunction "VDD3_14") (pintype "input"))
      (node (ref "U5") (pin "25") (pinfunction "SW_VDD3_25") (pintype "input"))
      (node (ref "U5") (pin "26") (pinfunction "SW_VDD3_26") (pintype "input"))
      (node (ref "U5") (pin "33") (pinfunction "VDD3_33") (pintype "input"))
      (node (ref "U5") (pin "43") (pinfunction "VDDA33_43") (pintype "input"))
    )
    (net (code "42") (name "VCC1.2V") (class "Default")
      (node (ref "C16") (pin "2") (pinfunction "2_2") (pintype "passive"))
      (node (ref "FB1") (pin "1") (pinfunction "1_1") (pintype "passive"))
      (node (ref "FB3") (pin "1") (pinfunction "1_1") (pintype "passive"))
      (node (ref "L6") (pin "1") (pinfunction "1_1") (pintype "passive"))
      (node (ref "U5") (pin "12") (pinfunction "VDD1_12") (pintype "input"))
      (node (ref "U5") (pin "20") (pinfunction "VDD1_20") (pintype "input"))
      (node (ref "U5") (pin "23") (pinfunction "FB_23") (pintype "input"))
      (node (ref "U5") (pin "28") (pinfunction "VDD1_28") (pintype "input"))
      (node (ref "U5") (pin "34") (pinfunction "VDD1_34") (pintype "input"))
      (node (ref "U5") (pin "42") (pinfunction "UVDDA_42") (pintype "input"))
    )
    (net (code "43") (name "VCC_5V") (class "Default")
      (node (ref "C29") (pin "2") (pinfunction "A_2") (pintype "passive"))
      (node (ref "C30") (pin "2") (pinfunction "2_2") (pintype "passive"))
      (node (ref "F1") (pin "1") (pinfunction "1_1") (pintype "passive"))
      (node (ref "U2") (pin "3") (pinfunction "VIN_3") (pintype "power_in"))
    )
    (net (code "44") (name "VCC_A1") (class "Default")
      (node (ref "C17") (pin "1") (pinfunction "1_1") (pintype "passive"))
      (node (ref "C18") (pin "2") (pinfunction "2_2") (pintype "passive"))
      (node (ref "C28") (pin "1") (pinfunction "1_1") (pintype "passive"))
      (node (ref "FB1") (pin "2") (pinfunction "2_2") (pintype "passive"))
      (node (ref "U5") (pin "44") (pinfunction "VDDA_44") (pintype "input"))
      (node (ref "U5") (pin "46") (pinfunction "VCMI_46") (pintype "input"))
      (node (ref "U5") (pin "47") (pinfunction "VDDA_47") (pintype "input"))
    )
    (net (code "45") (name "VCC_PLL") (class "Default")
      (node (ref "C19") (pin "1") (pinfunction "1_1") (pintype "passive"))
      (node (ref "C20") (pin "2") (pinfunction "2_2") (pintype "passive"))
      (node (ref "FB3") (pin "2") (pinfunction "2_2") (pintype "passive"))
      (node (ref "U5") (pin "7") (pinfunction "VDDPLL_7") (pintype "input"))
    )
    (net (code "46") (name "unconnected-(ANT1-Support_Pad-Pad2)") (class "Default")
      (node (ref "ANT1") (pin "2") (pinfunction "Support_Pad_2") (pintype "passive"))
    )
    (net (code "47") (name "unconnected-(U1-LT-Pad3)") (class "Default")
      (node (ref "U1") (pin "3") (pinfunction "LT_3") (pintype "passive"))
    )
    (net (code "48") (name "unconnected-(U1-NC-Pad1)") (class "Default")
      (node (ref "U1") (pin "1") (pinfunction "NC_1") (pintype "passive"))
    )
    (net (code "49") (name "unconnected-(U4-~{WC}-Pad7)") (class "Default")
      (node (ref "U4") (pin "7") (pinfunction "~{WC}_7") (pintype "input"))
    )
    (net (code "50") (name "unconnected-(U5-AGC_RF-Pad15)") (class "Default")
      (node (ref "U5") (pin "15") (pinfunction "AGC_RF_15") (pintype "input"))
    )
    (net (code "51") (name "unconnected-(U5-GPIO0-Pad37)") (class "Default")
      (node (ref "U5") (pin "37") (pinfunction "GPIO0_37") (pintype "input"))
    )
    (net (code "52") (name "unconnected-(U5-GPIO1-Pad32)") (class "Default")
      (node (ref "U5") (pin "32") (pinfunction "GPIO1_32") (pintype "input"))
    )
    (net (code "53") (name "unconnected-(U5-GPIO2-Pad31)") (class "Default")
      (node (ref "U5") (pin "31") (pinfunction "GPIO2_31") (pintype "input"))
    )
    (net (code "54") (name "unconnected-(U5-GPIO3-Pad36)") (class "Default")
      (node (ref "U5") (pin "36") (pinfunction "GPIO3_36") (pintype "input"))
    )
    (net (code "55") (name "unconnected-(U5-GPIO4-Pad30)") (class "Default")
      (node (ref "U5") (pin "30") (pinfunction "GPIO4_30") (pintype "input"))
    )
    (net (code "56") (name "unconnected-(U5-GPIO5-Pad29)") (class "Default")
      (node (ref "U5") (pin "29") (pinfunction "GPIO5_29") (pintype "input"))
    )
    (net (code "57") (name "unconnected-(U5-GPIO6-Pad22)") (class "Default")
      (node (ref "U5") (pin "22") (pinfunction "GPIO6_22") (pintype "input"))
    )
    (net (code "58") (name "unconnected-(U5-GPIO7-Pad21)") (class "Default")
      (node (ref "U5") (pin "21") (pinfunction "GPIO7_21") (pintype "input"))
    )
    (net (code "59") (name "unconnected-(U5-IR_RX_IN-Pad38)") (class "Default")
      (node (ref "U5") (pin "38") (pinfunction "IR_RX_IN_38") (pintype "input"))
    )
    (net (code "60") (name "unconnected-(U5-M_ERR-Pad35)") (class "Default")
      (node (ref "U5") (pin "35") (pinfunction "M_ERR_35") (pintype "input"))
    )
    (net (code "61") (name "unconnected-(U5-TP_CKO-Pad9)") (class "Default")
      (node (ref "U5") (pin "9") (pinfunction "TP_CKO_9") (pintype "input"))
    )
    (net (code "62") (name "unconnected-(U5-VINR-Pad6)") (class "Default")
      (node (ref "U5") (pin "6") (pinfunction "VINR_6") (pintype "input"))
    )
    (net (code "63") (name "unconnected-(U5-VQN-Pad5)") (class "Default")
      (node (ref "U5") (pin "5") (pinfunction "VQN_5") (pintype "input"))
    )
    (net (code "64") (name "unconnected-(U5-VQP-Pad4)") (class "Default")
      (node (ref "U5") (pin "4") (pinfunction "VQP_4") (pintype "input"))
    )
  )
)
